# WifeOLED-v2.net
KiCad netlist of a schematic drawn in EAGLE
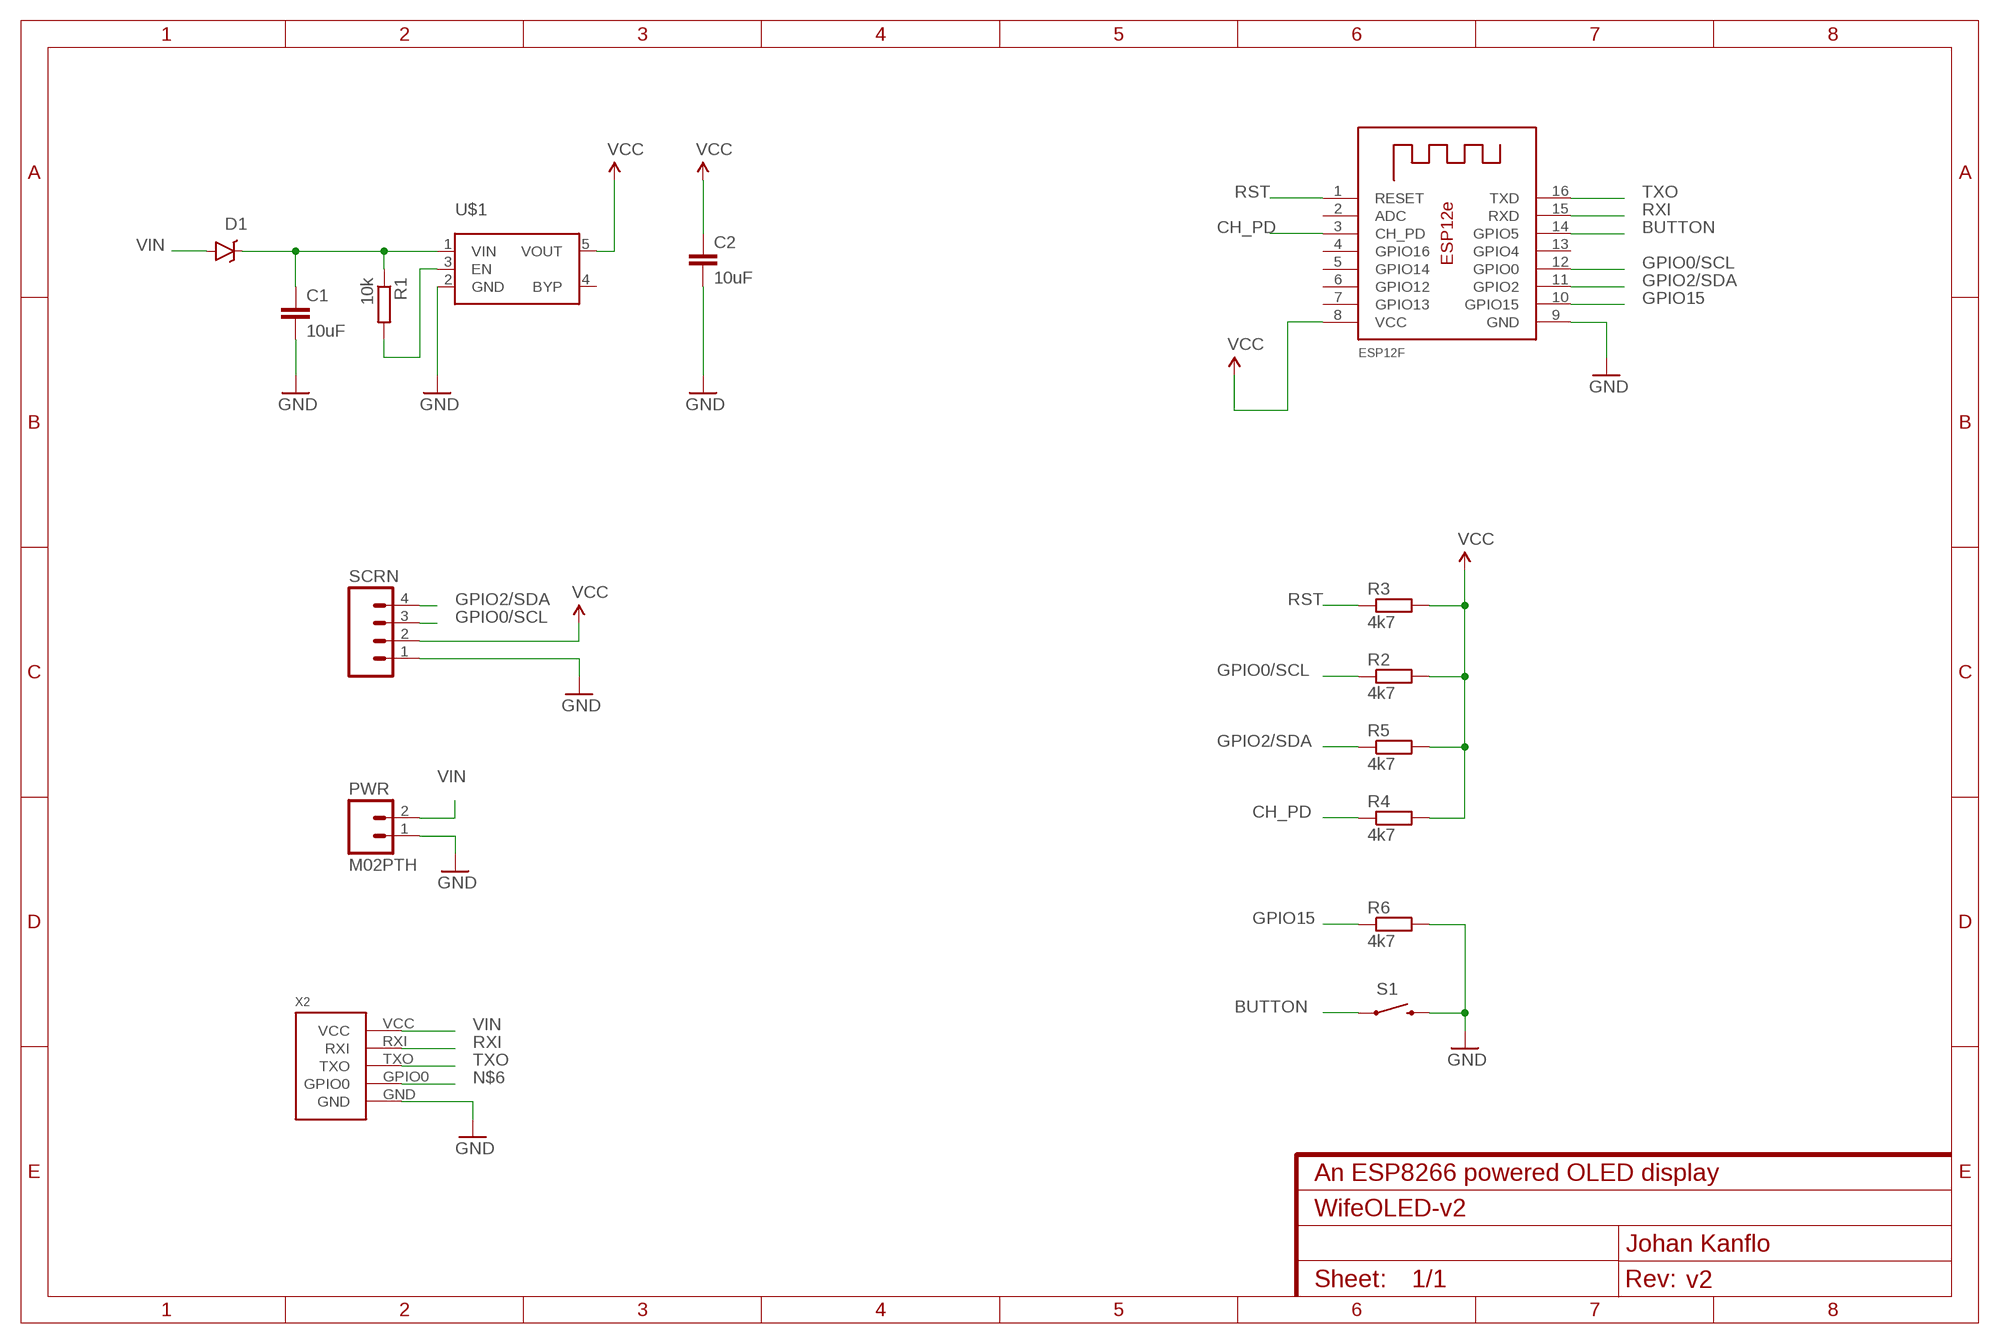
[diagram p0: schematic, sheet 1]

(export (version "E")
  (design (tool "Eeschema 10.0.6"))
  (components
    (comp (ref "C1")
      (value "10uF")
      (footprint "eagle-import:0603-CAP")
      (libsource (lib "eagle-import") (part "10UF-6.3V-20%(0603)"))
    )
    (comp (ref "C2")
      (value "10uF")
      (footprint "eagle-import:0603-CAP")
      (libsource (lib "eagle-import") (part "10UF-6.3V-20%(0603)"))
    )
    (comp (ref "D1")
      (value "DIODE-SCHOTTKYSOD-123FL")
      (footprint "eagle-import:SOD-123FL")
      (libsource (lib "eagle-import") (part "DIODE-SCHOTTKYSOD-123FL"))
    )
    (comp (ref "ESP12F")
      (value "ESP-12E")
      (footprint "eagle-import:ESP-12E")
      (libsource (lib "eagle-import") (part "ESP-12E"))
    )
    (comp (ref "PWR")
      (value "M02PTH")
      (footprint "eagle-import:1X02")
      (libsource (lib "eagle-import") (part "M02PTH"))
    )
    (comp (ref "R1")
      (value "10k")
      (footprint "eagle-import:R0603")
      (libsource (lib "eagle-import") (part "R-EU_R0603"))
    )
    (comp (ref "R2")
      (value "4k7")
      (footprint "eagle-import:R0603")
      (libsource (lib "eagle-import") (part "R-EU_R0603"))
    )
    (comp (ref "R3")
      (value "4k7")
      (footprint "eagle-import:R0603")
      (libsource (lib "eagle-import") (part "R-EU_R0603"))
    )
    (comp (ref "R4")
      (value "4k7")
      (footprint "eagle-import:R0603")
      (libsource (lib "eagle-import") (part "R-EU_R0603"))
    )
    (comp (ref "R5")
      (value "4k7")
      (footprint "eagle-import:R0603")
      (libsource (lib "eagle-import") (part "R-EU_R0603"))
    )
    (comp (ref "R6")
      (value "4k7")
      (footprint "eagle-import:R0603")
      (libsource (lib "eagle-import") (part "R-EU_R0603"))
    )
    (comp (ref "S1")
      (value "SWITCH-MOMENTARY-2SMD-1101NE")
      (footprint "eagle-import:TACTILE-SWITCH-1101NE")
      (libsource (lib "eagle-import") (part "SWITCH-MOMENTARY-2SMD-1101NE"))
    )
    (comp (ref "SCRN")
      (value "M04PTH")
      (footprint "eagle-import:1X04")
      (libsource (lib "eagle-import") (part "M04PTH"))
    )
    (comp (ref "U$1")
      (value "SPX3819")
      (footprint "eagle-import:SOT23-5")
      (libsource (lib "eagle-import") (part "SPX3819"))
    )
    (comp (ref "X2")
      (value "ESPROGESPROG-DEVICE")
      (footprint "eagle-import:ESPROG")
      (libsource (lib "eagle-import") (part "ESPROGESPROG-DEVICE"))
    )
  )
  (nets
    (net (code "1") (name "/BUTTON") (class "Default")
      (node (ref "ESP12F") (pin "14") (pinfunction "GPIO5_14") (pintype "bidirectional"))
      (node (ref "S1") (pin "1") (pinfunction "1_1") (pintype "passive"))
    )
    (net (code "2") (name "/CH_PD") (class "Default")
      (node (ref "ESP12F") (pin "3") (pinfunction "CH_PD_3") (pintype "input"))
      (node (ref "R4") (pin "1") (pinfunction "1_1") (pintype "passive"))
    )
    (net (code "3") (name "/GPIO0{slash}SCL") (class "Default")
      (node (ref "ESP12F") (pin "12") (pinfunction "GPIO0_12") (pintype "bidirectional"))
      (node (ref "R2") (pin "1") (pinfunction "1_1") (pintype "passive"))
      (node (ref "SCRN") (pin "3") (pinfunction "3_3") (pintype "passive"))
    )
    (net (code "4") (name "/GPIO2{slash}SDA") (class "Default")
      (node (ref "ESP12F") (pin "11") (pinfunction "GPIO2_11") (pintype "bidirectional"))
      (node (ref "R5") (pin "1") (pinfunction "1_1") (pintype "passive"))
      (node (ref "SCRN") (pin "4") (pinfunction "4_4") (pintype "passive"))
    )
    (net (code "5") (name "/GPIO15") (class "Default")
      (node (ref "ESP12F") (pin "10") (pinfunction "GPIO15_10") (pintype "bidirectional"))
      (node (ref "R6") (pin "1") (pinfunction "1_1") (pintype "passive"))
    )
    (net (code "6") (name "/N$6") (class "Default")
      (node (ref "X2") (pin "GPIO0") (pinfunction "GPIO0_GPIO0") (pintype "bidirectional"))
    )
    (net (code "7") (name "/RST") (class "Default")
      (node (ref "ESP12F") (pin "1") (pinfunction "RESET_1") (pintype "input"))
      (node (ref "R3") (pin "1") (pinfunction "1_1") (pintype "passive"))
    )
    (net (code "8") (name "/RXI") (class "Default")
      (node (ref "ESP12F") (pin "15") (pinfunction "RXD_15") (pintype "input"))
      (node (ref "X2") (pin "RXI") (pinfunction "RXI_RXI") (pintype "bidirectional"))
    )
    (net (code "9") (name "/TXO") (class "Default")
      (node (ref "ESP12F") (pin "16") (pinfunction "TXD_16") (pintype "output"))
      (node (ref "X2") (pin "TXO") (pinfunction "TXO_TXO") (pintype "bidirectional"))
    )
    (net (code "10") (name "/VIN") (class "Default")
      (node (ref "D1") (pin "A") (pinfunction "A_A") (pintype "passive"))
      (node (ref "PWR") (pin "2") (pinfunction "2_2") (pintype "passive"))
      (node (ref "X2") (pin "VCC") (pinfunction "VCC_VCC") (pintype "bidirectional"))
    )
    (net (code "11") (name "GND") (class "Default")
      (node (ref "C1") (pin "2") (pinfunction "2_2") (pintype "passive"))
      (node (ref "C2") (pin "2") (pinfunction "2_2") (pintype "passive"))
      (node (ref "ESP12F") (pin "9") (pinfunction "GND_9") (pintype "power_in"))
      (node (ref "PWR") (pin "1") (pinfunction "1_1") (pintype "passive"))
      (node (ref "R6") (pin "2") (pinfunction "2_2") (pintype "passive"))
      (node (ref "S1") (pin "2") (pinfunction "2_2") (pintype "passive"))
      (node (ref "SCRN") (pin "1") (pinfunction "1_1") (pintype "passive"))
      (node (ref "U$1") (pin "2") (pinfunction "GND_2") (pintype "power_in"))
      (node (ref "X2") (pin "GND") (pinfunction "GND_GND") (pintype "bidirectional"))
    )
    (net (code "12") (name "Net-(U$1-EN)") (class "Default")
      (node (ref "R1") (pin "2") (pinfunction "2_2") (pintype "passive"))
      (node (ref "U$1") (pin "3") (pinfunction "EN_3") (pintype "input"))
    )
    (net (code "13") (name "Net-(U$1-VIN)") (class "Default")
      (node (ref "C1") (pin "1") (pinfunction "1_1") (pintype "passive"))
      (node (ref "D1") (pin "C") (pinfunction "C_C") (pintype "passive"))
      (node (ref "R1") (pin "1") (pinfunction "1_1") (pintype "passive"))
      (node (ref "U$1") (pin "1") (pinfunction "VIN_1") (pintype "power_in"))
    )
    (net (code "14") (name "VCC") (class "Default")
      (node (ref "C2") (pin "1") (pinfunction "1_1") (pintype "passive"))
      (node (ref "ESP12F") (pin "8") (pinfunction "VCC_8") (pintype "power_in"))
      (node (ref "R2") (pin "2") (pinfunction "2_2") (pintype "passive"))
      (node (ref "R3") (pin "2") (pinfunction "2_2") (pintype "passive"))
      (node (ref "R4") (pin "2") (pinfunction "2_2") (pintype "passive"))
      (node (ref "R5") (pin "2") (pinfunction "2_2") (pintype "passive"))
      (node (ref "SCRN") (pin "2") (pinfunction "2_2") (pintype "passive"))
      (node (ref "U$1") (pin "5") (pinfunction "VOUT_5") (pintype "output"))
    )
    (net (code "15") (name "unconnected-(ESP12F-ADC-Pad2)") (class "Default")
      (node (ref "ESP12F") (pin "2") (pinfunction "ADC_2") (pintype "passive"))
    )
    (net (code "16") (name "unconnected-(ESP12F-GPIO4-Pad13)") (class "Default")
      (node (ref "ESP12F") (pin "13") (pinfunction "GPIO4_13") (pintype "bidirectional"))
    )
    (net (code "17") (name "unconnected-(ESP12F-GPIO12-Pad6)") (class "Default")
      (node (ref "ESP12F") (pin "6") (pinfunction "GPIO12_6") (pintype "bidirectional"))
    )
    (net (code "18") (name "unconnected-(ESP12F-GPIO13-Pad7)") (class "Default")
      (node (ref "ESP12F") (pin "7") (pinfunction "GPIO13_7") (pintype "bidirectional"))
    )
    (net (code "19") (name "unconnected-(ESP12F-GPIO14-Pad5)") (class "Default")
      (node (ref "ESP12F") (pin "5") (pinfunction "GPIO14_5") (pintype "bidirectional"))
    )
    (net (code "20") (name "unconnected-(ESP12F-GPIO16-Pad4)") (class "Default")
      (node (ref "ESP12F") (pin "4") (pinfunction "GPIO16_4") (pintype "bidirectional"))
    )
    (net (code "21") (name "unconnected-(U$1-BYP-Pad4)") (class "Default")
      (node (ref "U$1") (pin "4") (pinfunction "BYP_4") (pintype "output"))
    )
  )
)
